# Sheet1.net
KiCad netlist of a schematic drawn in Altium Designer
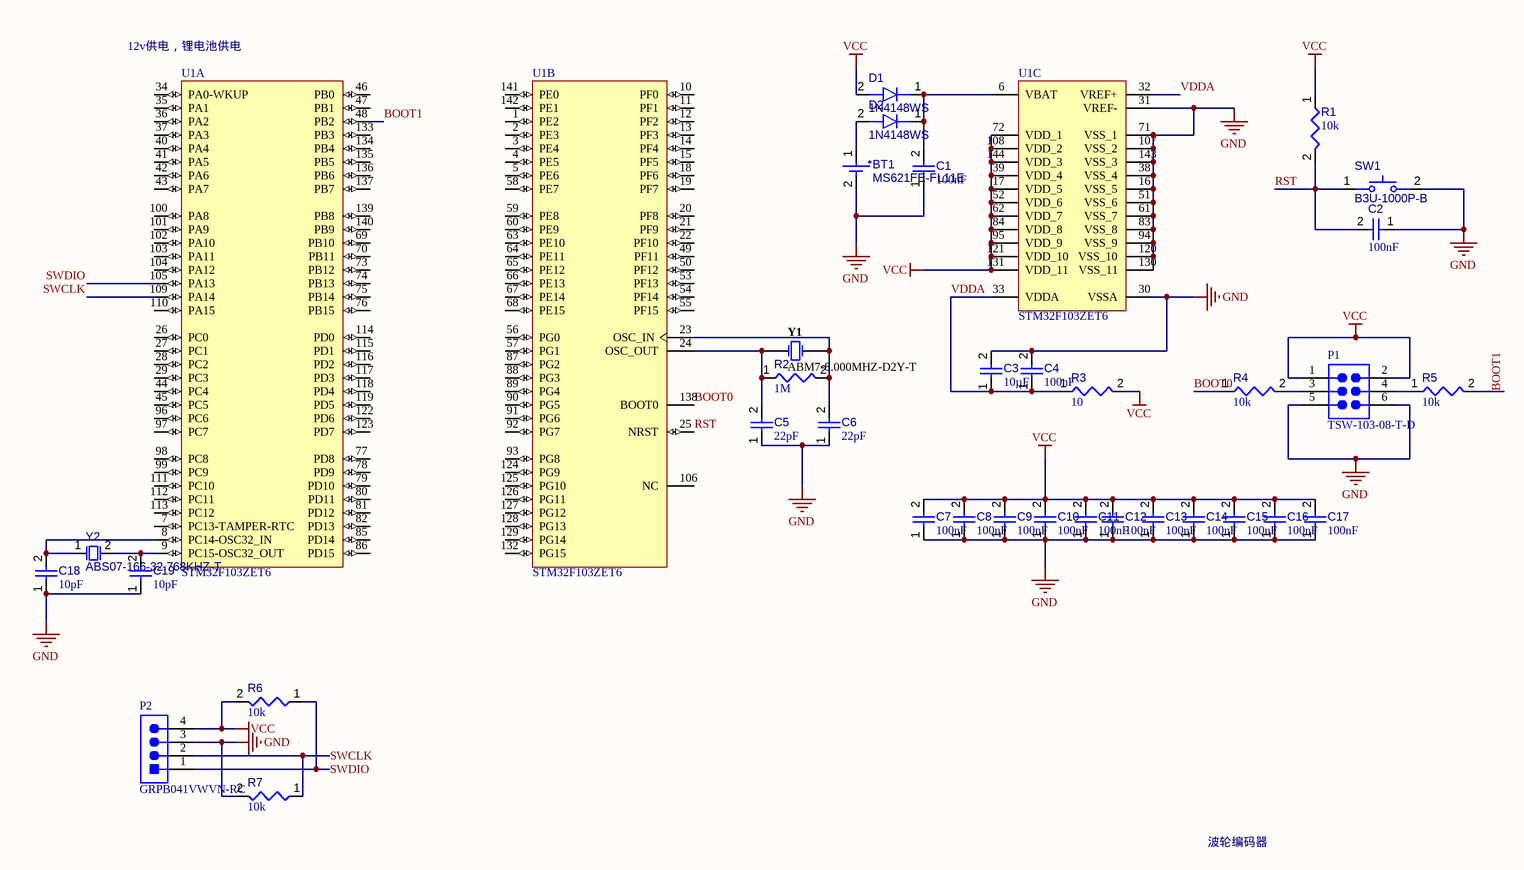
[diagram p0: Sheet1.SchDoc]

(export (version "E")
  (design (tool "Eeschema 10.0.6"))
  (components
    (comp (ref "BT1")
      (value "MS621FE-FL11E")
      (footprint "SEIK-MS621FE-FL11E-2_V")
      (description "MS Lihium Rechargeable Battery, 3 V, -20 to 60 degC, Tray")
      (libsource (lib "DigiPCBA Workspace") (part "CMP-00622-2"))
    )
    (comp (ref "C1")
      (value "100nF")
      (footprint "CAPC1608X90X40NL10T20")
      (description "Chip Capacitor, 100 nF, +/- 10%, 50 V, 0603 (1608 Metric)")
      (fields (field (name "TOLERANCE") "10%") (field (name "Comment") "Capacitor 100 nF +/-10% 50 V 0603"))
      (libsource (lib "DigiPCBA Workspace") (part "CAP-NP-2"))
    )
    (comp (ref "C2")
      (value "100nF")
      (footprint "CAPC1608X90X40NL10T20")
      (description "Chip Capacitor, 100 nF, +/- 10%, 50 V, 0603 (1608 Metric)")
      (fields (field (name "TOLERANCE") "10%") (field (name "Comment") "Capacitor 100 nF +/-10% 50 V 0603"))
      (libsource (lib "DigiPCBA Workspace") (part "CAP-NP-2"))
    )
    (comp (ref "C3")
      (value "10µF")
      (footprint "CAPC0603(1608)100_L")
      (description "Chip Capacitor, 10µF +/-20%, 10V, 0603, Thickness 1 mm")
      (fields (field (name "TOLERANCE") "10%") (field (name "Comment") "Capacitor 10µF +/-20% 10V 0603"))
      (libsource (lib "DigiPCBA Workspace") (part "CAP-NP-2"))
    )
    (comp (ref "C4")
      (value "100nF")
      (footprint "CAPC1608X90X40NL10T20")
      (description "Chip Capacitor, 100 nF, +/- 10%, 50 V, 0603 (1608 Metric)")
      (fields (field (name "TOLERANCE") "10%") (field (name "Comment") "Capacitor 100 nF +/-10% 50 V 0603"))
      (libsource (lib "DigiPCBA Workspace") (part "CAP-NP-2"))
    )
    (comp (ref "C5")
      (value "22pF")
      (footprint "CAPC1608X90X35ML10T15")
      (description "CAP CER 22PF 50V C0G/NP0 0603")
      (fields (field (name "TOLERANCE") "10%") (field (name "Comment") "GRM1885C1H220JA01D"))
      (libsource (lib "DigiPCBA Workspace") (part "CAP-NP-2"))
    )
    (comp (ref "C6")
      (value "22pF")
      (footprint "CAPC1608X90X35ML10T15")
      (description "CAP CER 22PF 50V C0G/NP0 0603")
      (fields (field (name "TOLERANCE") "10%") (field (name "Comment") "GRM1885C1H220JA01D"))
      (libsource (lib "DigiPCBA Workspace") (part "CAP-NP-2"))
    )
    (comp (ref "C7")
      (value "100nF")
      (footprint "CAPC1608X90X40NL10T20")
      (description "Chip Capacitor, 100 nF, +/- 10%, 50 V, 0603 (1608 Metric)")
      (fields (field (name "TOLERANCE") "10%") (field (name "Comment") "Capacitor 100 nF +/-10% 50 V 0603"))
      (libsource (lib "DigiPCBA Workspace") (part "CAP-NP-2"))
    )
    (comp (ref "C8")
      (value "100nF")
      (footprint "CAPC1608X90X40NL10T20")
      (description "Chip Capacitor, 100 nF, +/- 10%, 50 V, 0603 (1608 Metric)")
      (fields (field (name "TOLERANCE") "10%") (field (name "Comment") "Capacitor 100 nF +/-10% 50 V 0603"))
      (libsource (lib "DigiPCBA Workspace") (part "CAP-NP-2"))
    )
    (comp (ref "C9")
      (value "100nF")
      (footprint "CAPC1608X90X40NL10T20")
      (description "Chip Capacitor, 100 nF, +/- 10%, 50 V, 0603 (1608 Metric)")
      (fields (field (name "TOLERANCE") "10%") (field (name "Comment") "Capacitor 100 nF +/-10% 50 V 0603"))
      (libsource (lib "DigiPCBA Workspace") (part "CAP-NP-2"))
    )
    (comp (ref "C10")
      (value "100nF")
      (footprint "CAPC1608X90X40NL10T20")
      (description "Chip Capacitor, 100 nF, +/- 10%, 50 V, 0603 (1608 Metric)")
      (fields (field (name "TOLERANCE") "10%") (field (name "Comment") "Capacitor 100 nF +/-10% 50 V 0603"))
      (libsource (lib "DigiPCBA Workspace") (part "CAP-NP-2"))
    )
    (comp (ref "C11")
      (value "100nF")
      (footprint "CAPC1608X90X40NL10T20")
      (description "Chip Capacitor, 100 nF, +/- 10%, 50 V, 0603 (1608 Metric)")
      (fields (field (name "TOLERANCE") "10%") (field (name "Comment") "Capacitor 100 nF +/-10% 50 V 0603"))
      (libsource (lib "DigiPCBA Workspace") (part "CAP-NP-2"))
    )
    (comp (ref "C12")
      (value "100nF")
      (footprint "CAPC1608X90X40NL10T20")
      (description "Chip Capacitor, 100 nF, +/- 10%, 50 V, 0603 (1608 Metric)")
      (fields (field (name "TOLERANCE") "10%") (field (name "Comment") "Capacitor 100 nF +/-10% 50 V 0603"))
      (libsource (lib "DigiPCBA Workspace") (part "CAP-NP-2"))
    )
    (comp (ref "C13")
      (value "100nF")
      (footprint "CAPC1608X90X40NL10T20")
      (description "Chip Capacitor, 100 nF, +/- 10%, 50 V, 0603 (1608 Metric)")
      (fields (field (name "TOLERANCE") "10%") (field (name "Comment") "Capacitor 100 nF +/-10% 50 V 0603"))
      (libsource (lib "DigiPCBA Workspace") (part "CAP-NP-2"))
    )
    (comp (ref "C14")
      (value "100nF")
      (footprint "CAPC1608X90X40NL10T20")
      (description "Chip Capacitor, 100 nF, +/- 10%, 50 V, 0603 (1608 Metric)")
      (fields (field (name "TOLERANCE") "10%") (field (name "Comment") "Capacitor 100 nF +/-10% 50 V 0603"))
      (libsource (lib "DigiPCBA Workspace") (part "CAP-NP-2"))
    )
    (comp (ref "C15")
      (value "100nF")
      (footprint "CAPC1608X90X40NL10T20")
      (description "Chip Capacitor, 100 nF, +/- 10%, 50 V, 0603 (1608 Metric)")
      (fields (field (name "TOLERANCE") "10%") (field (name "Comment") "Capacitor 100 nF +/-10% 50 V 0603"))
      (libsource (lib "DigiPCBA Workspace") (part "CAP-NP-2"))
    )
    (comp (ref "C16")
      (value "100nF")
      (footprint "CAPC1608X90X40NL10T20")
      (description "Chip Capacitor, 100 nF, +/- 10%, 50 V, 0603 (1608 Metric)")
      (fields (field (name "TOLERANCE") "10%") (field (name "Comment") "Capacitor 100 nF +/-10% 50 V 0603"))
      (libsource (lib "DigiPCBA Workspace") (part "CAP-NP-2"))
    )
    (comp (ref "C17")
      (value "100nF")
      (footprint "CAPC1608X90X40NL10T20")
      (description "Chip Capacitor, 100 nF, +/- 10%, 50 V, 0603 (1608 Metric)")
      (fields (field (name "TOLERANCE") "10%") (field (name "Comment") "Capacitor 100 nF +/-10% 50 V 0603"))
      (libsource (lib "DigiPCBA Workspace") (part "CAP-NP-2"))
    )
    (comp (ref "C18")
      (value "10pF")
      (footprint "CAPC1005X55X25ML05T05")
      (description "Chip Capacitor, 10 pF, +/- 5%, 50 V, 0402 (1005 Metric)")
      (fields (field (name "TOLERANCE") "5%") (field (name "Comment") "Capacitor 10 pF +/- 5% 50 V 0402"))
      (libsource (lib "DigiPCBA Workspace") (part "CAP-NP-2"))
    )
    (comp (ref "C19")
      (value "10pF")
      (footprint "CAPC1005X55X25ML05T05")
      (description "Chip Capacitor, 10 pF, +/- 5%, 50 V, 0402 (1005 Metric)")
      (fields (field (name "TOLERANCE") "5%") (field (name "Comment") "Capacitor 10 pF +/- 5% 50 V 0402"))
      (libsource (lib "DigiPCBA Workspace") (part "CAP-NP-2"))
    )
    (comp (ref "D1")
      (value "1N4148WS")
      (footprint "FP-477AB-IPC_A")
      (description "Diode Ultra Fast Recovery Rectifier 75V 0.15A 2-Pin SOD-323F T/R")
      (libsource (lib "DigiPCBA Workspace") (part "DIODE-2"))
    )
    (comp (ref "D2")
      (value "1N4148WS")
      (footprint "FP-477AB-IPC_A")
      (description "Diode Ultra Fast Recovery Rectifier 75V 0.15A 2-Pin SOD-323F T/R")
      (libsource (lib "DigiPCBA Workspace") (part "DIODE-2"))
    )
    (comp (ref "P1")
      (value "TSW-103-08-T-D")
      (footprint "SMTC-TSW-103-08-X-D")
      (description "Headers & Wire Housings Classic PCB Header Strips, 0.100 pitch")
      (libsource (lib "DigiPCBA Workspace") (part "SMTC-TSW-103-08-X-D"))
    )
    (comp (ref "P2")
      (value "GRPB041VWVN-RC")
      (footprint "SLIN-GRPB041VWVN-RC_V")
      (description "Male, 4 C, Straight, .050\" CC; 3.00mm Head/2.30mm Tail, No Mt; Nylon 9T, Brass, 105 C")
      (libsource (lib "DigiPCBA Workspace") (part "CN-1P-M-R4"))
    )
    (comp (ref "R1")
      (value "10k")
      (footprint "RESC1608X55X25ML10T15")
      (description "Chip Resistor, 10 KOhm, +/- 1%, 01 W, -55 to 155 degC, 0603 (1608 Metric)")
      (fields (field (name "POWER") "100mW") (field (name "TOLERANCE") "1%"))
      (libsource (lib "DigiPCBA Workspace") (part "RES-2"))
    )
    (comp (ref "R2")
      (value "1M")
      (footprint "FP-ERJ3EK-IPC_A")
      (description "Res Thick Film 0603 1M Ohm 1% 1/10W ±100ppm/°C Molded SMD Punched Carrier T/R")
      (fields (field (name "TOLERANCE") "1%") (field (name "Comment") "ERJ-3EKF1004V"))
      (libsource (lib "DigiPCBA Workspace") (part "RES-2"))
    )
    (comp (ref "R3")
      (value "10")
      (footprint "RESC0603(1608)_L")
      (description "Res Thick Film 0603 10 Ohm 1% 0.1W(1/10W) +/-100ppm/C Molded SMD Automotive Punched T/R")
      (fields (field (name "TOLERANCE") "1%") (field (name "Comment") "ERJ3EKF10R0V"))
      (libsource (lib "DigiPCBA Workspace") (part "RES-2"))
    )
    (comp (ref "R4")
      (value "10k")
      (footprint "RESC1608X55X25ML10T15")
      (description "Chip Resistor, 10 KOhm, +/- 1%, 01 W, -55 to 155 degC, 0603 (1608 Metric)")
      (fields (field (name "POWER") "100mW") (field (name "TOLERANCE") "1%"))
      (libsource (lib "DigiPCBA Workspace") (part "RES-2"))
    )
    (comp (ref "R5")
      (value "10k")
      (footprint "RESC1608X55X25ML10T15")
      (description "Chip Resistor, 10 KOhm, +/- 1%, 01 W, -55 to 155 degC, 0603 (1608 Metric)")
      (fields (field (name "POWER") "100mW") (field (name "TOLERANCE") "1%"))
      (libsource (lib "DigiPCBA Workspace") (part "RES-2"))
    )
    (comp (ref "R6")
      (value "10k")
      (footprint "RESC1608X55X25ML10T15")
      (description "Chip Resistor, 10 KOhm, +/- 1%, 01 W, -55 to 155 degC, 0603 (1608 Metric)")
      (fields (field (name "POWER") "100mW") (field (name "TOLERANCE") "1%"))
      (libsource (lib "DigiPCBA Workspace") (part "RES-2"))
    )
    (comp (ref "R7")
      (value "10k")
      (footprint "RESC1608X55X25ML10T15")
      (description "Chip Resistor, 10 KOhm, +/- 1%, 01 W, -55 to 155 degC, 0603 (1608 Metric)")
      (fields (field (name "POWER") "100mW") (field (name "TOLERANCE") "1%"))
      (libsource (lib "DigiPCBA Workspace") (part "RES-2"))
    )
    (comp (ref "SW1")
      (value "B3U-1000P-B")
      (footprint "OMRON-B3U-1000P-2-B_V")
      (libsource (lib "DigiPCBA Workspace") (part "CMP-00164-6"))
    )
    (comp (ref "U1")
      (value "STM32F103ZET6")
      (footprint "STM-LQFP144_N")
      (description "MCU 32-bit STM32F1 ARM Cortex M3 RISC 512KB Flash 2.5V/3.3V 144-Pin LQFP Tray")
      (libsource (lib "DigiPCBA Workspace") (part "MC-ARM-STM32F103XC_D_E-SQ144"))
    )
    (comp (ref "Y1")
      (value "ABM7-8.000MHZ-D2Y-T")
      (footprint "FP-ABM7-MFG")
      (description "Crystal 8MHz ±20ppm (Tol) ±30ppm (Stability) 18pF FUND 100Ohm 2-Pin Mini-CSMD T/R")
      (libsource (lib "DigiPCBA Workspace") (part "XTAL-2"))
    )
    (comp (ref "Y2")
      (value "ABS07-166-32.768KHZ-T")
      (footprint "EPSON-FC-135_V")
      (description "Crystal 32.768kHz 10ppm 7pF -40C +85C")
      (libsource (lib "DigiPCBA Workspace") (part "CMP-001-0024-1"))
    )
  )
  (nets
    (net (code "1") (name "/BOOT0") (class "Default")
      (node (ref "R4") (pin "1") (pinfunction "1_1") (pintype "passive"))
      (node (ref "U1") (pin "138") (pinfunction "BOOT0_138") (pintype "passive"))
    )
    (net (code "2") (name "/BOOT1") (class "Default")
      (node (ref "R5") (pin "2") (pinfunction "2_2") (pintype "passive"))
      (node (ref "U1") (pin "48") (pinfunction "PB2_48") (pintype "bidirectional"))
    )
    (net (code "3") (name "/RST") (class "Default")
      (node (ref "C2") (pin "2") (pinfunction "2_2") (pintype "passive"))
      (node (ref "R1") (pin "2") (pinfunction "2_2") (pintype "passive"))
      (node (ref "SW1") (pin "1") (pinfunction "1_1") (pintype "passive"))
      (node (ref "U1") (pin "25") (pinfunction "NRST_25") (pintype "bidirectional"))
    )
    (net (code "4") (name "/SWCLK") (class "Default")
      (node (ref "P2") (pin "2") (pinfunction "2_2") (pintype "passive"))
      (node (ref "R7") (pin "1") (pinfunction "1_1") (pintype "passive"))
      (node (ref "U1") (pin "109") (pinfunction "PA14_109") (pintype "bidirectional"))
    )
    (net (code "5") (name "/SWDIO") (class "Default")
      (node (ref "P2") (pin "1") (pinfunction "1_1") (pintype "passive"))
      (node (ref "R6") (pin "1") (pinfunction "1_1") (pintype "passive"))
      (node (ref "U1") (pin "105") (pinfunction "PA13_105") (pintype "bidirectional"))
    )
    (net (code "6") (name "/VDDA") (class "Default")
      (node (ref "C3") (pin "1") (pinfunction "1_1") (pintype "passive"))
      (node (ref "C4") (pin "1") (pinfunction "1_1") (pintype "passive"))
      (node (ref "R3") (pin "1") (pinfunction "1_1") (pintype "passive"))
      (node (ref "U1") (pin "32") (pinfunction "VREF+_32") (pintype "power_in"))
      (node (ref "U1") (pin "33") (pinfunction "VDDA_33") (pintype "power_in"))
    )
    (net (code "7") (name "GND") (class "Default")
      (node (ref "BT1") (pin "2") (pinfunction "-_2") (pintype "passive"))
      (node (ref "C1") (pin "1") (pinfunction "1_1") (pintype "passive"))
      (node (ref "C10") (pin "1") (pinfunction "1_1") (pintype "passive"))
      (node (ref "C11") (pin "1") (pinfunction "1_1") (pintype "passive"))
      (node (ref "C12") (pin "1") (pinfunction "1_1") (pintype "passive"))
      (node (ref "C13") (pin "1") (pinfunction "1_1") (pintype "passive"))
      (node (ref "C14") (pin "1") (pinfunction "1_1") (pintype "passive"))
      (node (ref "C15") (pin "1") (pinfunction "1_1") (pintype "passive"))
      (node (ref "C16") (pin "1") (pinfunction "1_1") (pintype "passive"))
      (node (ref "C17") (pin "1") (pinfunction "1_1") (pintype "passive"))
      (node (ref "C18") (pin "1") (pinfunction "1_1") (pintype "passive"))
      (node (ref "C19") (pin "1") (pinfunction "1_1") (pintype "passive"))
      (node (ref "C2") (pin "1") (pinfunction "1_1") (pintype "passive"))
      (node (ref "C3") (pin "2") (pinfunction "2_2") (pintype "passive"))
      (node (ref "C4") (pin "2") (pinfunction "2_2") (pintype "passive"))
      (node (ref "C5") (pin "1") (pinfunction "1_1") (pintype "passive"))
      (node (ref "C6") (pin "1") (pinfunction "1_1") (pintype "passive"))
      (node (ref "C7") (pin "1") (pinfunction "1_1") (pintype "passive"))
      (node (ref "C8") (pin "1") (pinfunction "1_1") (pintype "passive"))
      (node (ref "C9") (pin "1") (pinfunction "1_1") (pintype "passive"))
      (node (ref "P1") (pin "5") (pinfunction "5_5") (pintype "passive"))
      (node (ref "P1") (pin "6") (pinfunction "6_6") (pintype "passive"))
      (node (ref "P2") (pin "3") (pinfunction "3_3") (pintype "passive"))
      (node (ref "R7") (pin "2") (pinfunction "2_2") (pintype "passive"))
      (node (ref "SW1") (pin "2") (pinfunction "2_2") (pintype "passive"))
      (node (ref "U1") (pin "107") (pinfunction "VSS_2_107") (pintype "power_in"))
      (node (ref "U1") (pin "120") (pinfunction "VSS_10_120") (pintype "power_in"))
      (node (ref "U1") (pin "130") (pinfunction "VSS_11_130") (pintype "power_in"))
      (node (ref "U1") (pin "143") (pinfunction "VSS_3_143") (pintype "power_in"))
      (node (ref "U1") (pin "16") (pinfunction "VSS_5_16") (pintype "power_in"))
      (node (ref "U1") (pin "30") (pinfunction "VSSA_30") (pintype "power_in"))
      (node (ref "U1") (pin "31") (pinfunction "VREF-_31") (pintype "power_in"))
      (node (ref "U1") (pin "38") (pinfunction "VSS_4_38") (pintype "power_in"))
      (node (ref "U1") (pin "51") (pinfunction "VSS_6_51") (pintype "power_in"))
      (node (ref "U1") (pin "61") (pinfunction "VSS_7_61") (pintype "power_in"))
      (node (ref "U1") (pin "71") (pinfunction "VSS_1_71") (pintype "power_in"))
      (node (ref "U1") (pin "83") (pinfunction "VSS_8_83") (pintype "power_in"))
      (node (ref "U1") (pin "94") (pinfunction "VSS_9_94") (pintype "power_in"))
    )
    (net (code "8") (name "Net-(BT1-+)") (class "Default")
      (node (ref "BT1") (pin "1") (pinfunction "+_1") (pintype "passive"))
      (node (ref "D2") (pin "2") (pinfunction "A_2") (pintype "passive"))
    )
    (net (code "9") (name "Net-(D1-K)") (class "Default")
      (node (ref "C1") (pin "2") (pinfunction "2_2") (pintype "passive"))
      (node (ref "D1") (pin "1") (pinfunction "K_1") (pintype "passive"))
      (node (ref "D2") (pin "1") (pinfunction "K_1") (pintype "passive"))
      (node (ref "U1") (pin "6") (pinfunction "VBAT_6") (pintype "power_in"))
    )
    (net (code "10") (name "Net-(P1-Pad3)") (class "Default")
      (node (ref "P1") (pin "3") (pinfunction "3_3") (pintype "passive"))
      (node (ref "R4") (pin "2") (pinfunction "2_2") (pintype "passive"))
    )
    (net (code "11") (name "Net-(P1-Pad4)") (class "Default")
      (node (ref "P1") (pin "4") (pinfunction "4_4") (pintype "passive"))
      (node (ref "R5") (pin "1") (pinfunction "1_1") (pintype "passive"))
    )
    (net (code "12") (name "Net-(U1A-PC14-OSC32_IN)") (class "Default")
      (node (ref "C18") (pin "2") (pinfunction "2_2") (pintype "passive"))
      (node (ref "U1") (pin "8") (pinfunction "PC14-OSC32_IN_8") (pintype "bidirectional"))
      (node (ref "Y2") (pin "1") (pinfunction "1_1") (pintype "passive"))
    )
    (net (code "13") (name "Net-(U1A-PC15-OSC32_OUT)") (class "Default")
      (node (ref "C19") (pin "2") (pinfunction "2_2") (pintype "passive"))
      (node (ref "U1") (pin "9") (pinfunction "PC15-OSC32_OUT_9") (pintype "bidirectional"))
      (node (ref "Y2") (pin "2") (pinfunction "2_2") (pintype "passive"))
    )
    (net (code "14") (name "Net-(U1B-OSC_IN)") (class "Default")
      (node (ref "C6") (pin "2") (pinfunction "2_2") (pintype "passive"))
      (node (ref "R2") (pin "2") (pinfunction "2_2") (pintype "passive"))
      (node (ref "U1") (pin "23") (pinfunction "OSC_IN_23") (pintype "passive"))
      (node (ref "Y1") (pin "2") (pinfunction "2_2") (pintype "passive"))
    )
    (net (code "15") (name "Net-(U1B-OSC_OUT)") (class "Default")
      (node (ref "C5") (pin "2") (pinfunction "2_2") (pintype "passive"))
      (node (ref "R2") (pin "1") (pinfunction "1_1") (pintype "passive"))
      (node (ref "U1") (pin "24") (pinfunction "OSC_OUT_24") (pintype "passive"))
      (node (ref "Y1") (pin "1") (pinfunction "1_1") (pintype "passive"))
    )
    (net (code "16") (name "VCC") (class "Default")
      (node (ref "C10") (pin "2") (pinfunction "2_2") (pintype "passive"))
      (node (ref "C11") (pin "2") (pinfunction "2_2") (pintype "passive"))
      (node (ref "C12") (pin "2") (pinfunction "2_2") (pintype "passive"))
      (node (ref "C13") (pin "2") (pinfunction "2_2") (pintype "passive"))
      (node (ref "C14") (pin "2") (pinfunction "2_2") (pintype "passive"))
      (node (ref "C15") (pin "2") (pinfunction "2_2") (pintype "passive"))
      (node (ref "C16") (pin "2") (pinfunction "2_2") (pintype "passive"))
      (node (ref "C17") (pin "2") (pinfunction "2_2") (pintype "passive"))
      (node (ref "C7") (pin "2") (pinfunction "2_2") (pintype "passive"))
      (node (ref "C8") (pin "2") (pinfunction "2_2") (pintype "passive"))
      (node (ref "C9") (pin "2") (pinfunction "2_2") (pintype "passive"))
      (node (ref "D1") (pin "2") (pinfunction "A_2") (pintype "passive"))
      (node (ref "P1") (pin "1") (pinfunction "1_1") (pintype "passive"))
      (node (ref "P1") (pin "2") (pinfunction "2_2") (pintype "passive"))
      (node (ref "P2") (pin "4") (pinfunction "4_4") (pintype "passive"))
      (node (ref "R1") (pin "1") (pinfunction "1_1") (pintype "passive"))
      (node (ref "R3") (pin "2") (pinfunction "2_2") (pintype "passive"))
      (node (ref "R6") (pin "2") (pinfunction "2_2") (pintype "passive"))
      (node (ref "U1") (pin "108") (pinfunction "VDD_2_108") (pintype "power_in"))
      (node (ref "U1") (pin "121") (pinfunction "VDD_10_121") (pintype "power_in"))
      (node (ref "U1") (pin "131") (pinfunction "VDD_11_131") (pintype "power_in"))
      (node (ref "U1") (pin "144") (pinfunction "VDD_3_144") (pintype "power_in"))
      (node (ref "U1") (pin "17") (pinfunction "VDD_5_17") (pintype "power_in"))
      (node (ref "U1") (pin "39") (pinfunction "VDD_4_39") (pintype "power_in"))
      (node (ref "U1") (pin "52") (pinfunction "VDD_6_52") (pintype "power_in"))
      (node (ref "U1") (pin "62") (pinfunction "VDD_7_62") (pintype "power_in"))
      (node (ref "U1") (pin "72") (pinfunction "VDD_1_72") (pintype "power_in"))
      (node (ref "U1") (pin "84") (pinfunction "VDD_8_84") (pintype "power_in"))
      (node (ref "U1") (pin "95") (pinfunction "VDD_9_95") (pintype "power_in"))
    )
    (net (code "17") (name "unconnected-(U1A-PA0-WKUP-Pad34)") (class "Default")
      (node (ref "U1") (pin "34") (pinfunction "PA0-WKUP_34") (pintype "bidirectional"))
    )
    (net (code "18") (name "unconnected-(U1A-PA1-Pad35)") (class "Default")
      (node (ref "U1") (pin "35") (pinfunction "PA1_35") (pintype "bidirectional"))
    )
    (net (code "19") (name "unconnected-(U1A-PA2-Pad36)") (class "Default")
      (node (ref "U1") (pin "36") (pinfunction "PA2_36") (pintype "bidirectional"))
    )
    (net (code "20") (name "unconnected-(U1A-PA3-Pad37)") (class "Default")
      (node (ref "U1") (pin "37") (pinfunction "PA3_37") (pintype "bidirectional"))
    )
    (net (code "21") (name "unconnected-(U1A-PA4-Pad40)") (class "Default")
      (node (ref "U1") (pin "40") (pinfunction "PA4_40") (pintype "bidirectional"))
    )
    (net (code "22") (name "unconnected-(U1A-PA5-Pad41)") (class "Default")
      (node (ref "U1") (pin "41") (pinfunction "PA5_41") (pintype "bidirectional"))
    )
    (net (code "23") (name "unconnected-(U1A-PA6-Pad42)") (class "Default")
      (node (ref "U1") (pin "42") (pinfunction "PA6_42") (pintype "bidirectional"))
    )
    (net (code "24") (name "unconnected-(U1A-PA7-Pad43)") (class "Default")
      (node (ref "U1") (pin "43") (pinfunction "PA7_43") (pintype "bidirectional"))
    )
    (net (code "25") (name "unconnected-(U1A-PA8-Pad100)") (class "Default")
      (node (ref "U1") (pin "100") (pinfunction "PA8_100") (pintype "bidirectional"))
    )
    (net (code "26") (name "unconnected-(U1A-PA9-Pad101)") (class "Default")
      (node (ref "U1") (pin "101") (pinfunction "PA9_101") (pintype "bidirectional"))
    )
    (net (code "27") (name "unconnected-(U1A-PA10-Pad102)") (class "Default")
      (node (ref "U1") (pin "102") (pinfunction "PA10_102") (pintype "bidirectional"))
    )
    (net (code "28") (name "unconnected-(U1A-PA11-Pad103)") (class "Default")
      (node (ref "U1") (pin "103") (pinfunction "PA11_103") (pintype "bidirectional"))
    )
    (net (code "29") (name "unconnected-(U1A-PA12-Pad104)") (class "Default")
      (node (ref "U1") (pin "104") (pinfunction "PA12_104") (pintype "bidirectional"))
    )
    (net (code "30") (name "unconnected-(U1A-PA15-Pad110)") (class "Default")
      (node (ref "U1") (pin "110") (pinfunction "PA15_110") (pintype "bidirectional"))
    )
    (net (code "31") (name "unconnected-(U1A-PB0-Pad46)") (class "Default")
      (node (ref "U1") (pin "46") (pinfunction "PB0_46") (pintype "bidirectional"))
    )
    (net (code "32") (name "unconnected-(U1A-PB1-Pad47)") (class "Default")
      (node (ref "U1") (pin "47") (pinfunction "PB1_47") (pintype "bidirectional"))
    )
    (net (code "33") (name "unconnected-(U1A-PB3-Pad133)") (class "Default")
      (node (ref "U1") (pin "133") (pinfunction "PB3_133") (pintype "bidirectional"))
    )
    (net (code "34") (name "unconnected-(U1A-PB4-Pad134)") (class "Default")
      (node (ref "U1") (pin "134") (pinfunction "PB4_134") (pintype "bidirectional"))
    )
    (net (code "35") (name "unconnected-(U1A-PB5-Pad135)") (class "Default")
      (node (ref "U1") (pin "135") (pinfunction "PB5_135") (pintype "bidirectional"))
    )
    (net (code "36") (name "unconnected-(U1A-PB6-Pad136)") (class "Default")
      (node (ref "U1") (pin "136") (pinfunction "PB6_136") (pintype "bidirectional"))
    )
    (net (code "37") (name "unconnected-(U1A-PB7-Pad137)") (class "Default")
      (node (ref "U1") (pin "137") (pinfunction "PB7_137") (pintype "bidirectional"))
    )
    (net (code "38") (name "unconnected-(U1A-PB8-Pad139)") (class "Default")
      (node (ref "U1") (pin "139") (pinfunction "PB8_139") (pintype "bidirectional"))
    )
    (net (code "39") (name "unconnected-(U1A-PB9-Pad140)") (class "Default")
      (node (ref "U1") (pin "140") (pinfunction "PB9_140") (pintype "bidirectional"))
    )
    (net (code "40") (name "unconnected-(U1A-PB10-Pad69)") (class "Default")
      (node (ref "U1") (pin "69") (pinfunction "PB10_69") (pintype "bidirectional"))
    )
    (net (code "41") (name "unconnected-(U1A-PB11-Pad70)") (class "Default")
      (node (ref "U1") (pin "70") (pinfunction "PB11_70") (pintype "bidirectional"))
    )
    (net (code "42") (name "unconnected-(U1A-PB12-Pad73)") (class "Default")
      (node (ref "U1") (pin "73") (pinfunction "PB12_73") (pintype "bidirectional"))
    )
    (net (code "43") (name "unconnected-(U1A-PB13-Pad74)") (class "Default")
      (node (ref "U1") (pin "74") (pinfunction "PB13_74") (pintype "bidirectional"))
    )
    (net (code "44") (name "unconnected-(U1A-PB14-Pad75)") (class "Default")
      (node (ref "U1") (pin "75") (pinfunction "PB14_75") (pintype "bidirectional"))
    )
    (net (code "45") (name "unconnected-(U1A-PB15-Pad76)") (class "Default")
      (node (ref "U1") (pin "76") (pinfunction "PB15_76") (pintype "bidirectional"))
    )
    (net (code "46") (name "unconnected-(U1A-PC0-Pad26)") (class "Default")
      (node (ref "U1") (pin "26") (pinfunction "PC0_26") (pintype "bidirectional"))
    )
    (net (code "47") (name "unconnected-(U1A-PC1-Pad27)") (class "Default")
      (node (ref "U1") (pin "27") (pinfunction "PC1_27") (pintype "bidirectional"))
    )
    (net (code "48") (name "unconnected-(U1A-PC2-Pad28)") (class "Default")
      (node (ref "U1") (pin "28") (pinfunction "PC2_28") (pintype "bidirectional"))
    )
    (net (code "49") (name "unconnected-(U1A-PC3-Pad29)") (class "Default")
      (node (ref "U1") (pin "29") (pinfunction "PC3_29") (pintype "bidirectional"))
    )
    (net (code "50") (name "unconnected-(U1A-PC4-Pad44)") (class "Default")
      (node (ref "U1") (pin "44") (pinfunction "PC4_44") (pintype "bidirectional"))
    )
    (net (code "51") (name "unconnected-(U1A-PC5-Pad45)") (class "Default")
      (node (ref "U1") (pin "45") (pinfunction "PC5_45") (pintype "bidirectional"))
    )
    (net (code "52") (name "unconnected-(U1A-PC6-Pad96)") (class "Default")
      (node (ref "U1") (pin "96") (pinfunction "PC6_96") (pintype "bidirectional"))
    )
    (net (code "53") (name "unconnected-(U1A-PC7-Pad97)") (class "Default")
      (node (ref "U1") (pin "97") (pinfunction "PC7_97") (pintype "bidirectional"))
    )
    (net (code "54") (name "unconnected-(U1A-PC8-Pad98)") (class "Default")
      (node (ref "U1") (pin "98") (pinfunction "PC8_98") (pintype "bidirectional"))
    )
    (net (code "55") (name "unconnected-(U1A-PC9-Pad99)") (class "Default")
      (node (ref "U1") (pin "99") (pinfunction "PC9_99") (pintype "bidirectional"))
    )
    (net (code "56") (name "unconnected-(U1A-PC10-Pad111)") (class "Default")
      (node (ref "U1") (pin "111") (pinfunction "PC10_111") (pintype "bidirectional"))
    )
    (net (code "57") (name "unconnected-(U1A-PC11-Pad112)") (class "Default")
      (node (ref "U1") (pin "112") (pinfunction "PC11_112") (pintype "bidirectional"))
    )
    (net (code "58") (name "unconnected-(U1A-PC12-Pad113)") (class "Default")
      (node (ref "U1") (pin "113") (pinfunction "PC12_113") (pintype "bidirectional"))
    )
    (net (code "59") (name "unconnected-(U1A-PC13-TAMPER-RTC-Pad7)") (class "Default")
      (node (ref "U1") (pin "7") (pinfunction "PC13-TAMPER-RTC_7") (pintype "bidirectional"))
    )
    (net (code "60") (name "unconnected-(U1A-PD0-Pad114)") (class "Default")
      (node (ref "U1") (pin "114") (pinfunction "PD0_114") (pintype "bidirectional"))
    )
    (net (code "61") (name "unconnected-(U1A-PD1-Pad115)") (class "Default")
      (node (ref "U1") (pin "115") (pinfunction "PD1_115") (pintype "bidirectional"))
    )
    (net (code "62") (name "unconnected-(U1A-PD2-Pad116)") (class "Default")
      (node (ref "U1") (pin "116") (pinfunction "PD2_116") (pintype "bidirectional"))
    )
    (net (code "63") (name "unconnected-(U1A-PD3-Pad117)") (class "Default")
      (node (ref "U1") (pin "117") (pinfunction "PD3_117") (pintype "bidirectional"))
    )
    (net (code "64") (name "unconnected-(U1A-PD4-Pad118)") (class "Default")
      (node (ref "U1") (pin "118") (pinfunction "PD4_118") (pintype "bidirectional"))
    )
    (net (code "65") (name "unconnected-(U1A-PD5-Pad119)") (class "Default")
      (node (ref "U1") (pin "119") (pinfunction "PD5_119") (pintype "bidirectional"))
    )
    (net (code "66") (name "unconnected-(U1A-PD6-Pad122)") (class "Default")
      (node (ref "U1") (pin "122") (pinfunction "PD6_122") (pintype "bidirectional"))
    )
    (net (code "67") (name "unconnected-(U1A-PD7-Pad123)") (class "Default")
      (node (ref "U1") (pin "123") (pinfunction "PD7_123") (pintype "bidirectional"))
    )
    (net (code "68") (name "unconnected-(U1A-PD8-Pad77)") (class "Default")
      (node (ref "U1") (pin "77") (pinfunction "PD8_77") (pintype "bidirectional"))
    )
    (net (code "69") (name "unconnected-(U1A-PD9-Pad78)") (class "Default")
      (node (ref "U1") (pin "78") (pinfunction "PD9_78") (pintype "bidirectional"))
    )
    (net (code "70") (name "unconnected-(U1A-PD10-Pad79)") (class "Default")
      (node (ref "U1") (pin "79") (pinfunction "PD10_79") (pintype "bidirectional"))
    )
    (net (code "71") (name "unconnected-(U1A-PD11-Pad80)") (class "Default")
      (node (ref "U1") (pin "80") (pinfunction "PD11_80") (pintype "bidirectional"))
    )
    (net (code "72") (name "unconnected-(U1A-PD12-Pad81)") (class "Default")
      (node (ref "U1") (pin "81") (pinfunction "PD12_81") (pintype "bidirectional"))
    )
    (net (code "73") (name "unconnected-(U1A-PD13-Pad82)") (class "Default")
      (node (ref "U1") (pin "82") (pinfunction "PD13_82") (pintype "bidirectional"))
    )
    (net (code "74") (name "unconnected-(U1A-PD14-Pad85)") (class "Default")
      (node (ref "U1") (pin "85") (pinfunction "PD14_85") (pintype "bidirectional"))
    )
    (net (code "75") (name "unconnected-(U1A-PD15-Pad86)") (class "Default")
      (node (ref "U1") (pin "86") (pinfunction "PD15_86") (pintype "bidirectional"))
    )
    (net (code "76") (name "unconnected-(U1B-NC-Pad106)") (class "Default")
      (node (ref "U1") (pin "106") (pinfunction "NC_106") (pintype "passive"))
    )
    (net (code "77") (name "unconnected-(U1B-PE0-Pad141)") (class "Default")
      (node (ref "U1") (pin "141") (pinfunction "PE0_141") (pintype "bidirectional"))
    )
    (net (code "78") (name "unconnected-(U1B-PE1-Pad142)") (class "Default")
      (node (ref "U1") (pin "142") (pinfunction "PE1_142") (pintype "bidirectional"))
    )
    (net (code "79") (name "unconnected-(U1B-PE2-Pad1)") (class "Default")
      (node (ref "U1") (pin "1") (pinfunction "PE2_1") (pintype "bidirectional"))
    )
    (net (code "80") (name "unconnected-(U1B-PE3-Pad2)") (class "Default")
      (node (ref "U1") (pin "2") (pinfunction "PE3_2") (pintype "bidirectional"))
    )
    (net (code "81") (name "unconnected-(U1B-PE4-Pad3)") (class "Default")
      (node (ref "U1") (pin "3") (pinfunction "PE4_3") (pintype "bidirectional"))
    )
    (net (code "82") (name "unconnected-(U1B-PE5-Pad4)") (class "Default")
      (node (ref "U1") (pin "4") (pinfunction "PE5_4") (pintype "bidirectional"))
    )
    (net (code "83") (name "unconnected-(U1B-PE6-Pad5)") (class "Default")
      (node (ref "U1") (pin "5") (pinfunction "PE6_5") (pintype "bidirectional"))
    )
    (net (code "84") (name "unconnected-(U1B-PE7-Pad58)") (class "Default")
      (node (ref "U1") (pin "58") (pinfunction "PE7_58") (pintype "bidirectional"))
    )
    (net (code "85") (name "unconnected-(U1B-PE8-Pad59)") (class "Default")
      (node (ref "U1") (pin "59") (pinfunction "PE8_59") (pintype "bidirectional"))
    )
    (net (code "86") (name "unconnected-(U1B-PE9-Pad60)") (class "Default")
      (node (ref "U1") (pin "60") (pinfunction "PE9_60") (pintype "bidirectional"))
    )
    (net (code "87") (name "unconnected-(U1B-PE10-Pad63)") (class "Default")
      (node (ref "U1") (pin "63") (pinfunction "PE10_63") (pintype "bidirectional"))
    )
    (net (code "88") (name "unconnected-(U1B-PE11-Pad64)") (class "Default")
      (node (ref "U1") (pin "64") (pinfunction "PE11_64") (pintype "bidirectional"))
    )
    (net (code "89") (name "unconnected-(U1B-PE12-Pad65)") (class "Default")
      (node (ref "U1") (pin "65") (pinfunction "PE12_65") (pintype "bidirectional"))
    )
    (net (code "90") (name "unconnected-(U1B-PE13-Pad66)") (class "Default")
      (node (ref "U1") (pin "66") (pinfunction "PE13_66") (pintype "bidirectional"))
    )
    (net (code "91") (name "unconnected-(U1B-PE14-Pad67)") (class "Default")
      (node (ref "U1") (pin "67") (pinfunction "PE14_67") (pintype "bidirectional"))
    )
    (net (code "92") (name "unconnected-(U1B-PE15-Pad68)") (class "Default")
      (node (ref "U1") (pin "68") (pinfunction "PE15_68") (pintype "bidirectional"))
    )
    (net (code "93") (name "unconnected-(U1B-PF0-Pad10)") (class "Default")
      (node (ref "U1") (pin "10") (pinfunction "PF0_10") (pintype "bidirectional"))
    )
    (net (code "94") (name "unconnected-(U1B-PF1-Pad11)") (class "Default")
      (node (ref "U1") (pin "11") (pinfunction "PF1_11") (pintype "bidirectional"))
    )
    (net (code "95") (name "unconnected-(U1B-PF2-Pad12)") (class "Default")
      (node (ref "U1") (pin "12") (pinfunction "PF2_12") (pintype "bidirectional"))
    )
    (net (code "96") (name "unconnected-(U1B-PF3-Pad13)") (class "Default")
      (node (ref "U1") (pin "13") (pinfunction "PF3_13") (pintype "bidirectional"))
    )
    (net (code "97") (name "unconnected-(U1B-PF4-Pad14)") (class "Default")
      (node (ref "U1") (pin "14") (pinfunction "PF4_14") (pintype "bidirectional"))
    )
    (net (code "98") (name "unconnected-(U1B-PF5-Pad15)") (class "Default")
      (node (ref "U1") (pin "15") (pinfunction "PF5_15") (pintype "bidirectional"))
    )
    (net (code "99") (name "unconnected-(U1B-PF6-Pad18)") (class "Default")
      (node (ref "U1") (pin "18") (pinfunction "PF6_18") (pintype "bidirectional"))
    )
    (net (code "100") (name "unconnected-(U1B-PF7-Pad19)") (class "Default")
      (node (ref "U1") (pin "19") (pinfunction "PF7_19") (pintype "bidirectional"))
    )
    (net (code "101") (name "unconnected-(U1B-PF8-Pad20)") (class "Default")
      (node (ref "U1") (pin "20") (pinfunction "PF8_20") (pintype "bidirectional"))
    )
    (net (code "102") (name "unconnected-(U1B-PF9-Pad21)") (class "Default")
      (node (ref "U1") (pin "21") (pinfunction "PF9_21") (pintype "bidirectional"))
    )
    (net (code "103") (name "unconnected-(U1B-PF10-Pad22)") (class "Default")
      (node (ref "U1") (pin "22") (pinfunction "PF10_22") (pintype "bidirectional"))
    )
    (net (code "104") (name "unconnected-(U1B-PF11-Pad49)") (class "Default")
      (node (ref "U1") (pin "49") (pinfunction "PF11_49") (pintype "bidirectional"))
    )
    (net (code "105") (name "unconnected-(U1B-PF12-Pad50)") (class "Default")
      (node (ref "U1") (pin "50") (pinfunction "PF12_50") (pintype "bidirectional"))
    )
    (net (code "106") (name "unconnected-(U1B-PF13-Pad53)") (class "Default")
      (node (ref "U1") (pin "53") (pinfunction "PF13_53") (pintype "bidirectional"))
    )
    (net (code "107") (name "unconnected-(U1B-PF14-Pad54)") (class "Default")
      (node (ref "U1") (pin "54") (pinfunction "PF14_54") (pintype "bidirectional"))
    )
    (net (code "108") (name "unconnected-(U1B-PF15-Pad55)") (class "Default")
      (node (ref "U1") (pin "55") (pinfunction "PF15_55") (pintype "bidirectional"))
    )
    (net (code "109") (name "unconnected-(U1B-PG0-Pad56)") (class "Default")
      (node (ref "U1") (pin "56") (pinfunction "PG0_56") (pintype "bidirectional"))
    )
    (net (code "110") (name "unconnected-(U1B-PG1-Pad57)") (class "Default")
      (node (ref "U1") (pin "57") (pinfunction "PG1_57") (pintype "bidirectional"))
    )
    (net (code "111") (name "unconnected-(U1B-PG2-Pad87)") (class "Default")
      (node (ref "U1") (pin "87") (pinfunction "PG2_87") (pintype "bidirectional"))
    )
    (net (code "112") (name "unconnected-(U1B-PG3-Pad88)") (class "Default")
      (node (ref "U1") (pin "88") (pinfunction "PG3_88") (pintype "bidirectional"))
    )
    (net (code "113") (name "unconnected-(U1B-PG4-Pad89)") (class "Default")
      (node (ref "U1") (pin "89") (pinfunction "PG4_89") (pintype "bidirectional"))
    )
    (net (code "114") (name "unconnected-(U1B-PG5-Pad90)") (class "Default")
      (node (ref "U1") (pin "90") (pinfunction "PG5_90") (pintype "bidirectional"))
    )
    (net (code "115") (name "unconnected-(U1B-PG6-Pad91)") (class "Default")
      (node (ref "U1") (pin "91") (pinfunction "PG6_91") (pintype "bidirectional"))
    )
    (net (code "116") (name "unconnected-(U1B-PG7-Pad92)") (class "Default")
      (node (ref "U1") (pin "92") (pinfunction "PG7_92") (pintype "bidirectional"))
    )
    (net (code "117") (name "unconnected-(U1B-PG8-Pad93)") (class "Default")
      (node (ref "U1") (pin "93") (pinfunction "PG8_93") (pintype "bidirectional"))
    )
    (net (code "118") (name "unconnected-(U1B-PG9-Pad124)") (class "Default")
      (node (ref "U1") (pin "124") (pinfunction "PG9_124") (pintype "bidirectional"))
    )
    (net (code "119") (name "unconnected-(U1B-PG10-Pad125)") (class "Default")
      (node (ref "U1") (pin "125") (pinfunction "PG10_125") (pintype "bidirectional"))
    )
    (net (code "120") (name "unconnected-(U1B-PG11-Pad126)") (class "Default")
      (node (ref "U1") (pin "126") (pinfunction "PG11_126") (pintype "bidirectional"))
    )
    (net (code "121") (name "unconnected-(U1B-PG12-Pad127)") (class "Default")
      (node (ref "U1") (pin "127") (pinfunction "PG12_127") (pintype "bidirectional"))
    )
    (net (code "122") (name "unconnected-(U1B-PG13-Pad128)") (class "Default")
      (node (ref "U1") (pin "128") (pinfunction "PG13_128") (pintype "bidirectional"))
    )
    (net (code "123") (name "unconnected-(U1B-PG14-Pad129)") (class "Default")
      (node (ref "U1") (pin "129") (pinfunction "PG14_129") (pintype "bidirectional"))
    )
    (net (code "124") (name "unconnected-(U1B-PG15-Pad132)") (class "Default")
      (node (ref "U1") (pin "132") (pinfunction "PG15_132") (pintype "bidirectional"))
    )
  )
)
